# NewWiring.net
KiCad netlist of a schematic drawn in EAGLE
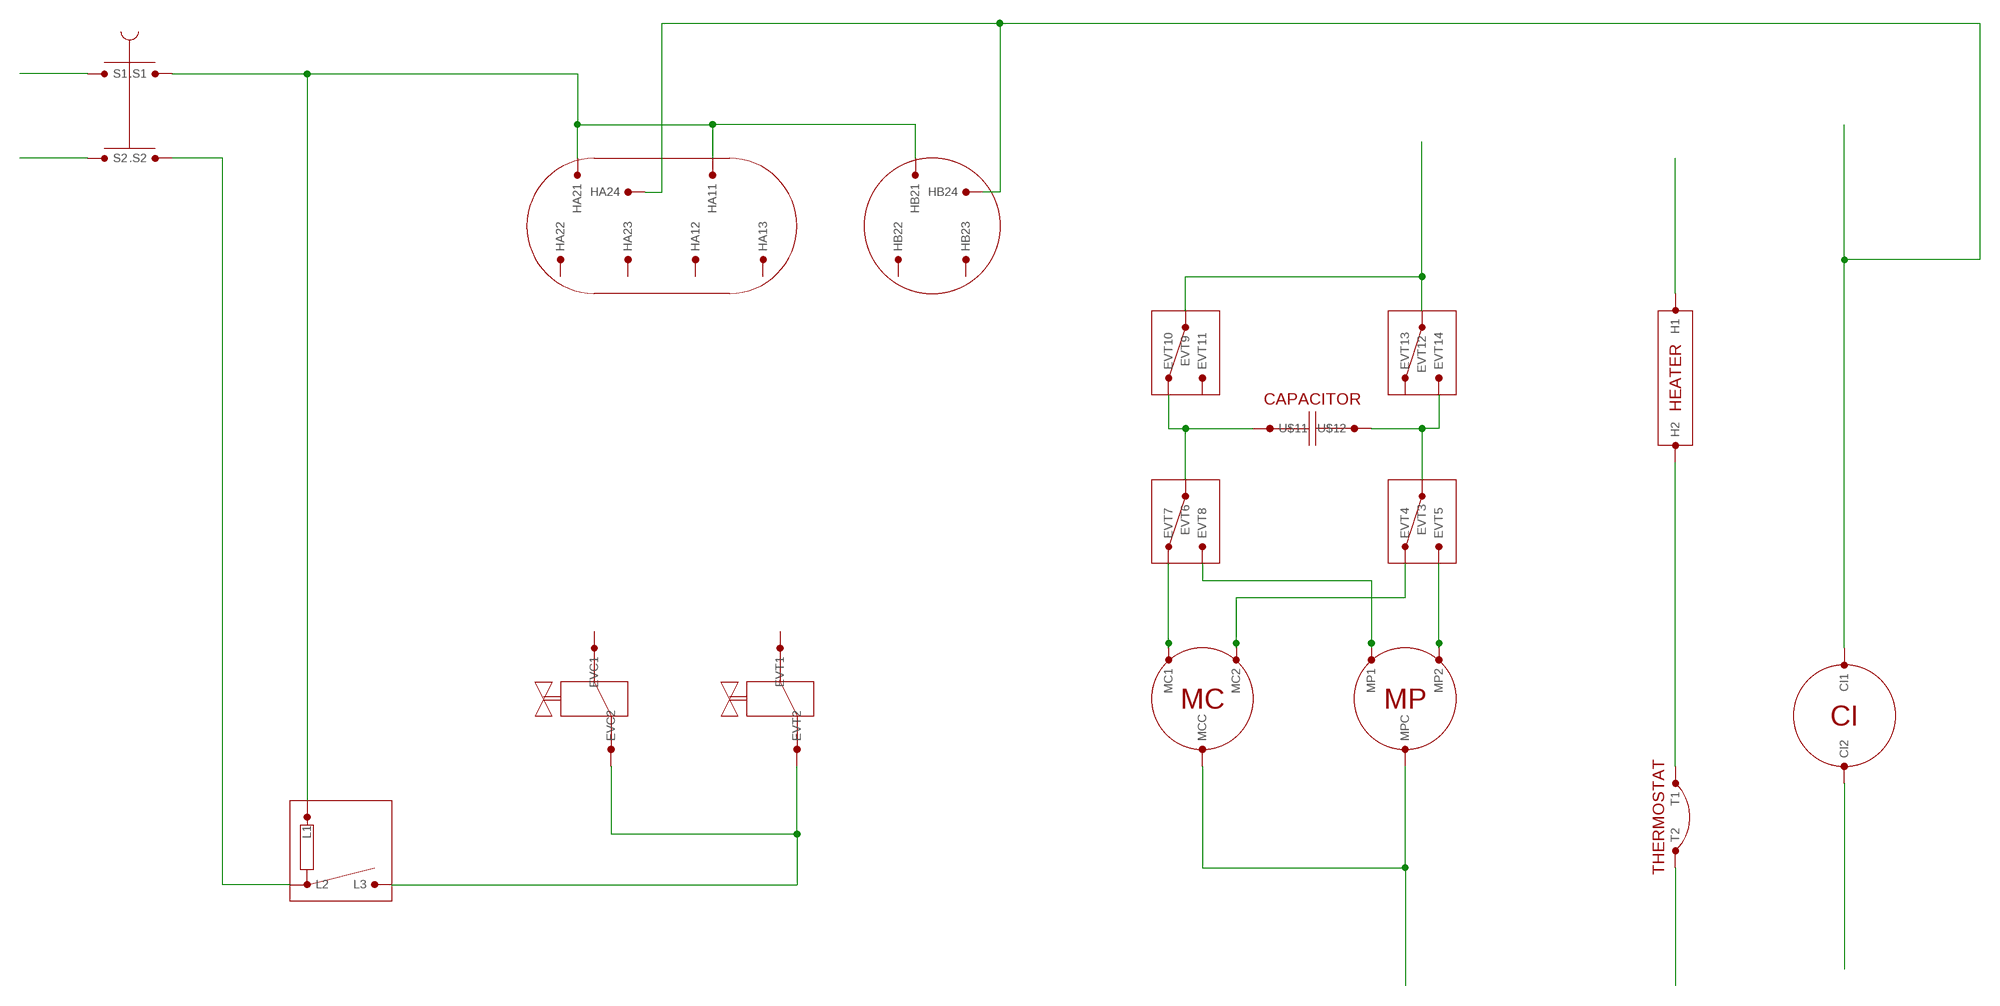
[diagram p0: schematic, sheet 1]

(export (version "E")
  (design (tool "Eeschema 10.0.6"))
  (components
    (comp (ref ".S1")
      (value "PIN")
      (footprint "eagle-import:PIN")
      (libsource (lib "eagle-import") (part "PIN"))
    )
    (comp (ref ".S2")
      (value "PIN")
      (footprint "eagle-import:PIN")
      (libsource (lib "eagle-import") (part "PIN"))
    )
    (comp (ref "CI1")
      (value "PIN")
      (footprint "eagle-import:PIN")
      (libsource (lib "eagle-import") (part "PIN"))
    )
    (comp (ref "CI2")
      (value "PIN")
      (footprint "eagle-import:PIN")
      (libsource (lib "eagle-import") (part "PIN"))
    )
    (comp (ref "EVC1")
      (value "PIN")
      (footprint "eagle-import:PIN")
      (libsource (lib "eagle-import") (part "PIN"))
    )
    (comp (ref "EVC2")
      (value "PIN")
      (footprint "eagle-import:PIN")
      (libsource (lib "eagle-import") (part "PIN"))
    )
    (comp (ref "EVT1")
      (value "PIN")
      (footprint "eagle-import:PIN")
      (libsource (lib "eagle-import") (part "PIN"))
    )
    (comp (ref "EVT2")
      (value "PIN")
      (footprint "eagle-import:PIN")
      (libsource (lib "eagle-import") (part "PIN"))
    )
    (comp (ref "EVT3")
      (value "PIN")
      (footprint "eagle-import:PIN")
      (libsource (lib "eagle-import") (part "PIN"))
    )
    (comp (ref "EVT4")
      (value "PIN")
      (footprint "eagle-import:PIN")
      (libsource (lib "eagle-import") (part "PIN"))
    )
    (comp (ref "EVT5")
      (value "PIN")
      (footprint "eagle-import:PIN")
      (libsource (lib "eagle-import") (part "PIN"))
    )
    (comp (ref "EVT6")
      (value "PIN")
      (footprint "eagle-import:PIN")
      (libsource (lib "eagle-import") (part "PIN"))
    )
    (comp (ref "EVT7")
      (value "PIN")
      (footprint "eagle-import:PIN")
      (libsource (lib "eagle-import") (part "PIN"))
    )
    (comp (ref "EVT8")
      (value "PIN")
      (footprint "eagle-import:PIN")
      (libsource (lib "eagle-import") (part "PIN"))
    )
    (comp (ref "EVT9")
      (value "PIN")
      (footprint "eagle-import:PIN")
      (libsource (lib "eagle-import") (part "PIN"))
    )
    (comp (ref "EVT10")
      (value "PIN")
      (footprint "eagle-import:PIN")
      (libsource (lib "eagle-import") (part "PIN"))
    )
    (comp (ref "EVT11")
      (value "PIN")
      (footprint "eagle-import:PIN")
      (libsource (lib "eagle-import") (part "PIN"))
    )
    (comp (ref "EVT12")
      (value "PIN")
      (footprint "eagle-import:PIN")
      (libsource (lib "eagle-import") (part "PIN"))
    )
    (comp (ref "EVT13")
      (value "PIN")
      (footprint "eagle-import:PIN")
      (libsource (lib "eagle-import") (part "PIN"))
    )
    (comp (ref "EVT14")
      (value "PIN")
      (footprint "eagle-import:PIN")
      (libsource (lib "eagle-import") (part "PIN"))
    )
    (comp (ref "H1")
      (value "PIN")
      (footprint "eagle-import:PIN")
      (libsource (lib "eagle-import") (part "PIN"))
    )
    (comp (ref "H2")
      (value "PIN")
      (footprint "eagle-import:PIN")
      (libsource (lib "eagle-import") (part "PIN"))
    )
    (comp (ref "HA11")
      (value "PIN")
      (footprint "eagle-import:PIN")
      (libsource (lib "eagle-import") (part "PIN"))
    )
    (comp (ref "HA12")
      (value "PIN")
      (footprint "eagle-import:PIN")
      (libsource (lib "eagle-import") (part "PIN"))
    )
    (comp (ref "HA13")
      (value "PIN")
      (footprint "eagle-import:PIN")
      (libsource (lib "eagle-import") (part "PIN"))
    )
    (comp (ref "HA21")
      (value "PIN")
      (footprint "eagle-import:PIN")
      (libsource (lib "eagle-import") (part "PIN"))
    )
    (comp (ref "HA22")
      (value "PIN")
      (footprint "eagle-import:PIN")
      (libsource (lib "eagle-import") (part "PIN"))
    )
    (comp (ref "HA23")
      (value "PIN")
      (footprint "eagle-import:PIN")
      (libsource (lib "eagle-import") (part "PIN"))
    )
    (comp (ref "HA24")
      (value "PIN")
      (footprint "eagle-import:PIN")
      (libsource (lib "eagle-import") (part "PIN"))
    )
    (comp (ref "HB21")
      (value "PIN")
      (footprint "eagle-import:PIN")
      (libsource (lib "eagle-import") (part "PIN"))
    )
    (comp (ref "HB22")
      (value "PIN")
      (footprint "eagle-import:PIN")
      (libsource (lib "eagle-import") (part "PIN"))
    )
    (comp (ref "HB23")
      (value "PIN")
      (footprint "eagle-import:PIN")
      (libsource (lib "eagle-import") (part "PIN"))
    )
    (comp (ref "HB24")
      (value "PIN")
      (footprint "eagle-import:PIN")
      (libsource (lib "eagle-import") (part "PIN"))
    )
    (comp (ref "L1")
      (value "PIN")
      (footprint "eagle-import:PIN")
      (libsource (lib "eagle-import") (part "PIN"))
    )
    (comp (ref "L2")
      (value "PIN")
      (footprint "eagle-import:PIN")
      (libsource (lib "eagle-import") (part "PIN"))
    )
    (comp (ref "L3")
      (value "PIN")
      (footprint "eagle-import:PIN")
      (libsource (lib "eagle-import") (part "PIN"))
    )
    (comp (ref "MC1")
      (value "PIN")
      (footprint "eagle-import:PIN")
      (libsource (lib "eagle-import") (part "PIN"))
    )
    (comp (ref "MC2")
      (value "PIN")
      (footprint "eagle-import:PIN")
      (libsource (lib "eagle-import") (part "PIN"))
    )
    (comp (ref "MCC")
      (value "PIN")
      (footprint "eagle-import:PIN")
      (libsource (lib "eagle-import") (part "PIN"))
    )
    (comp (ref "MP1")
      (value "PIN")
      (footprint "eagle-import:PIN")
      (libsource (lib "eagle-import") (part "PIN"))
    )
    (comp (ref "MP2")
      (value "PIN")
      (footprint "eagle-import:PIN")
      (libsource (lib "eagle-import") (part "PIN"))
    )
    (comp (ref "MPC")
      (value "PIN")
      (footprint "eagle-import:PIN")
      (libsource (lib "eagle-import") (part "PIN"))
    )
    (comp (ref "S1")
      (value "PIN")
      (footprint "eagle-import:PIN")
      (libsource (lib "eagle-import") (part "PIN"))
    )
    (comp (ref "S2")
      (value "PIN")
      (footprint "eagle-import:PIN")
      (libsource (lib "eagle-import") (part "PIN"))
    )
    (comp (ref "T1")
      (value "PIN")
      (footprint "eagle-import:PIN")
      (libsource (lib "eagle-import") (part "PIN"))
    )
    (comp (ref "T2")
      (value "PIN")
      (footprint "eagle-import:PIN")
      (libsource (lib "eagle-import") (part "PIN"))
    )
    (comp (ref "U$11")
      (value "PIN")
      (footprint "eagle-import:PIN")
      (libsource (lib "eagle-import") (part "PIN"))
    )
    (comp (ref "U$12")
      (value "PIN")
      (footprint "eagle-import:PIN")
      (libsource (lib "eagle-import") (part "PIN"))
    )
  )
  (nets
    (net (code "1") (name "Net-(.S1-PIN1)") (class "Default")
      (node (ref ".S1") (pin "P$1") (pinfunction "PIN1_P$1") (pintype "bidirectional"))
      (node (ref "HA11") (pin "P$1") (pinfunction "PIN1_P$1") (pintype "bidirectional"))
      (node (ref "HA21") (pin "P$1") (pinfunction "PIN1_P$1") (pintype "bidirectional"))
      (node (ref "HB21") (pin "P$1") (pinfunction "PIN1_P$1") (pintype "bidirectional"))
      (node (ref "L1") (pin "P$1") (pinfunction "PIN1_P$1") (pintype "bidirectional"))
    )
    (net (code "2") (name "Net-(.S2-PIN1)") (class "Default")
      (node (ref ".S2") (pin "P$1") (pinfunction "PIN1_P$1") (pintype "bidirectional"))
      (node (ref "L2") (pin "P$1") (pinfunction "PIN1_P$1") (pintype "bidirectional"))
    )
    (net (code "3") (name "Net-(CI1-PIN1)") (class "Default")
      (node (ref "CI1") (pin "P$1") (pinfunction "PIN1_P$1") (pintype "bidirectional"))
      (node (ref "HA24") (pin "P$1") (pinfunction "PIN1_P$1") (pintype "bidirectional"))
      (node (ref "HB24") (pin "P$1") (pinfunction "PIN1_P$1") (pintype "bidirectional"))
    )
    (net (code "4") (name "Net-(EVC2-PIN1)") (class "Default")
      (node (ref "EVC2") (pin "P$1") (pinfunction "PIN1_P$1") (pintype "bidirectional"))
      (node (ref "EVT2") (pin "P$1") (pinfunction "PIN1_P$1") (pintype "bidirectional"))
      (node (ref "L3") (pin "P$1") (pinfunction "PIN1_P$1") (pintype "bidirectional"))
    )
    (net (code "5") (name "Net-(EVT4-PIN1)") (class "Default")
      (node (ref "EVT4") (pin "P$1") (pinfunction "PIN1_P$1") (pintype "bidirectional"))
      (node (ref "MC2") (pin "P$1") (pinfunction "PIN1_P$1") (pintype "bidirectional"))
    )
    (net (code "6") (name "Net-(EVT5-PIN1)") (class "Default")
      (node (ref "EVT5") (pin "P$1") (pinfunction "PIN1_P$1") (pintype "bidirectional"))
      (node (ref "MP2") (pin "P$1") (pinfunction "PIN1_P$1") (pintype "bidirectional"))
    )
    (net (code "7") (name "Net-(EVT7-PIN1)") (class "Default")
      (node (ref "EVT7") (pin "P$1") (pinfunction "PIN1_P$1") (pintype "bidirectional"))
      (node (ref "MC1") (pin "P$1") (pinfunction "PIN1_P$1") (pintype "bidirectional"))
    )
    (net (code "8") (name "Net-(EVT8-PIN1)") (class "Default")
      (node (ref "EVT8") (pin "P$1") (pinfunction "PIN1_P$1") (pintype "bidirectional"))
      (node (ref "MP1") (pin "P$1") (pinfunction "PIN1_P$1") (pintype "bidirectional"))
    )
    (net (code "9") (name "Net-(EVT10-PIN1)") (class "Default")
      (node (ref "EVT10") (pin "P$1") (pinfunction "PIN1_P$1") (pintype "bidirectional"))
      (node (ref "EVT6") (pin "P$1") (pinfunction "PIN1_P$1") (pintype "bidirectional"))
      (node (ref "U$11") (pin "P$1") (pinfunction "PIN1_P$1") (pintype "bidirectional"))
    )
    (net (code "10") (name "Net-(EVT12-PIN1)") (class "Default")
      (node (ref "EVT12") (pin "P$1") (pinfunction "PIN1_P$1") (pintype "bidirectional"))
      (node (ref "EVT9") (pin "P$1") (pinfunction "PIN1_P$1") (pintype "bidirectional"))
    )
    (net (code "11") (name "Net-(EVT14-PIN1)") (class "Default")
      (node (ref "EVT14") (pin "P$1") (pinfunction "PIN1_P$1") (pintype "bidirectional"))
      (node (ref "EVT3") (pin "P$1") (pinfunction "PIN1_P$1") (pintype "bidirectional"))
      (node (ref "U$12") (pin "P$1") (pinfunction "PIN1_P$1") (pintype "bidirectional"))
    )
    (net (code "12") (name "Net-(H2-PIN1)") (class "Default")
      (node (ref "H2") (pin "P$1") (pinfunction "PIN1_P$1") (pintype "bidirectional"))
      (node (ref "T1") (pin "P$1") (pinfunction "PIN1_P$1") (pintype "bidirectional"))
    )
    (net (code "13") (name "Net-(MCC-PIN1)") (class "Default")
      (node (ref "MCC") (pin "P$1") (pinfunction "PIN1_P$1") (pintype "bidirectional"))
      (node (ref "MPC") (pin "P$1") (pinfunction "PIN1_P$1") (pintype "bidirectional"))
    )
    (net (code "14") (name "unconnected-(CI2-PIN1-PadP$1)") (class "Default")
      (node (ref "CI2") (pin "P$1") (pinfunction "PIN1_P$1") (pintype "bidirectional"))
    )
    (net (code "15") (name "unconnected-(EVC1-PIN1-PadP$1)") (class "Default")
      (node (ref "EVC1") (pin "P$1") (pinfunction "PIN1_P$1") (pintype "bidirectional"))
    )
    (net (code "16") (name "unconnected-(EVT1-PIN1-PadP$1)") (class "Default")
      (node (ref "EVT1") (pin "P$1") (pinfunction "PIN1_P$1") (pintype "bidirectional"))
    )
    (net (code "17") (name "unconnected-(EVT11-PIN1-PadP$1)") (class "Default")
      (node (ref "EVT11") (pin "P$1") (pinfunction "PIN1_P$1") (pintype "bidirectional"))
    )
    (net (code "18") (name "unconnected-(EVT13-PIN1-PadP$1)") (class "Default")
      (node (ref "EVT13") (pin "P$1") (pinfunction "PIN1_P$1") (pintype "bidirectional"))
    )
    (net (code "19") (name "unconnected-(H1-PIN1-PadP$1)") (class "Default")
      (node (ref "H1") (pin "P$1") (pinfunction "PIN1_P$1") (pintype "bidirectional"))
    )
    (net (code "20") (name "unconnected-(HA12-PIN1-PadP$1)") (class "Default")
      (node (ref "HA12") (pin "P$1") (pinfunction "PIN1_P$1") (pintype "bidirectional"))
    )
    (net (code "21") (name "unconnected-(HA13-PIN1-PadP$1)") (class "Default")
      (node (ref "HA13") (pin "P$1") (pinfunction "PIN1_P$1") (pintype "bidirectional"))
    )
    (net (code "22") (name "unconnected-(HA22-PIN1-PadP$1)") (class "Default")
      (node (ref "HA22") (pin "P$1") (pinfunction "PIN1_P$1") (pintype "bidirectional"))
    )
    (net (code "23") (name "unconnected-(HA23-PIN1-PadP$1)") (class "Default")
      (node (ref "HA23") (pin "P$1") (pinfunction "PIN1_P$1") (pintype "bidirectional"))
    )
    (net (code "24") (name "unconnected-(HB22-PIN1-PadP$1)") (class "Default")
      (node (ref "HB22") (pin "P$1") (pinfunction "PIN1_P$1") (pintype "bidirectional"))
    )
    (net (code "25") (name "unconnected-(HB23-PIN1-PadP$1)") (class "Default")
      (node (ref "HB23") (pin "P$1") (pinfunction "PIN1_P$1") (pintype "bidirectional"))
    )
    (net (code "26") (name "unconnected-(S1-PIN1-PadP$1)") (class "Default")
      (node (ref "S1") (pin "P$1") (pinfunction "PIN1_P$1") (pintype "bidirectional"))
    )
    (net (code "27") (name "unconnected-(S2-PIN1-PadP$1)") (class "Default")
      (node (ref "S2") (pin "P$1") (pinfunction "PIN1_P$1") (pintype "bidirectional"))
    )
    (net (code "28") (name "unconnected-(T2-PIN1-PadP$1)") (class "Default")
      (node (ref "T2") (pin "P$1") (pinfunction "PIN1_P$1") (pintype "bidirectional"))
    )
  )
)
